# 02-bluetooth-V2_2.net
KiCad netlist of a schematic drawn in Altium Designer
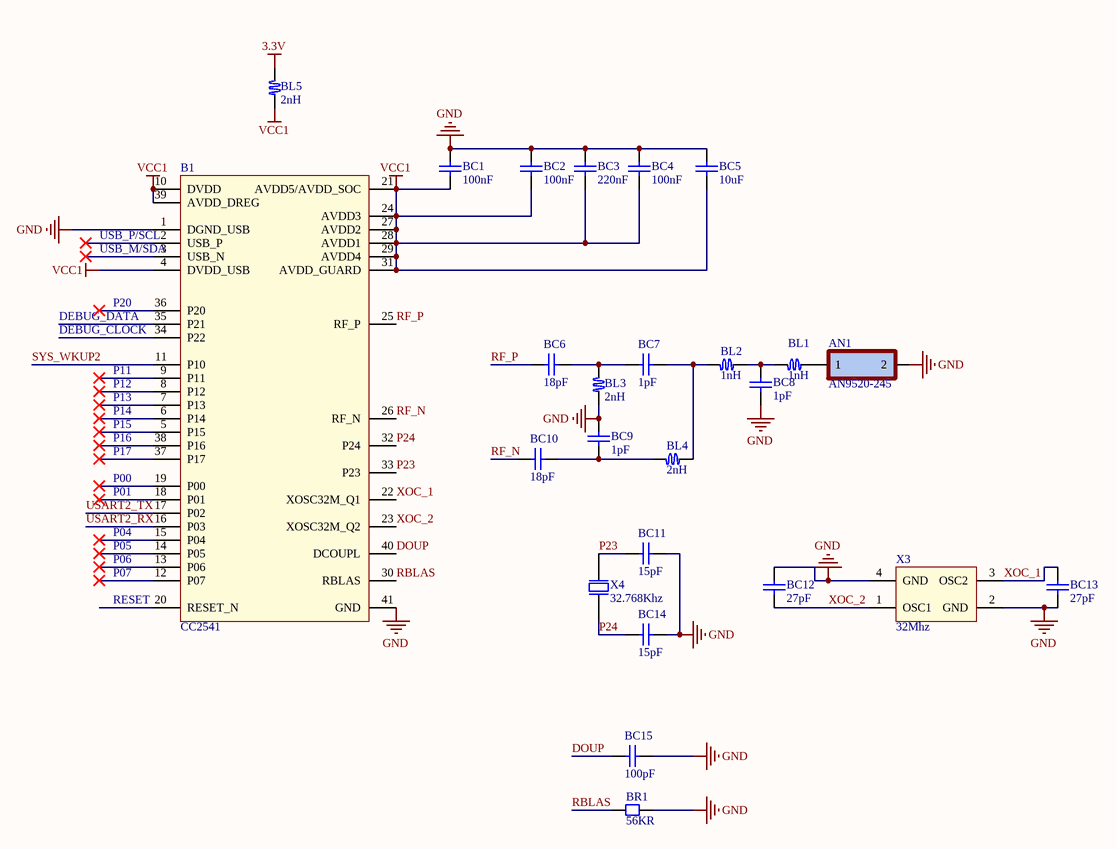
[diagram p0: 02-bluetooth-V2.2.SchDoc]

(export (version "E")
  (design (tool "Eeschema 10.0.6"))
  (components
    (comp (ref "AN1")
      (value "AN9520-245")
      (footprint "AN-5120")
      (description "2.4G全向天线 蓝牙天线 陶瓷贴片 WIFI内置")
      (libsource (lib "tianxiaohua_Schlib") (part "AN9520-245"))
    )
    (comp (ref "B1")
      (value "CC2541")
      (footprint "QFN40-CC254X")
      (description "低功耗蓝牙芯片")
      (libsource (lib "tianxiaohua_Schlib") (part "CC2541"))
    )
    (comp (ref "BC1")
      (value "100nF")
      (footprint "CC1005-0402")
      (description "贴片电容")
      (libsource (lib "tianxiaohua_Schlib") (part "Chip capacitor"))
    )
    (comp (ref "BC2")
      (value "100nF")
      (footprint "CC1005-0402")
      (description "贴片电容")
      (libsource (lib "tianxiaohua_Schlib") (part "Chip capacitor"))
    )
    (comp (ref "BC3")
      (value "220nF")
      (footprint "CC1005-0402")
      (description "贴片电容")
      (libsource (lib "tianxiaohua_Schlib") (part "Chip capacitor"))
    )
    (comp (ref "BC4")
      (value "100nF")
      (footprint "CC1005-0402")
      (description "贴片电容")
      (libsource (lib "tianxiaohua_Schlib") (part "Chip capacitor"))
    )
    (comp (ref "BC5")
      (value "10uF")
      (footprint "CC1005-0402")
      (description "贴片电容")
      (libsource (lib "tianxiaohua_Schlib") (part "Chip capacitor"))
    )
    (comp (ref "BC6")
      (value "18pF")
      (footprint "CC1005-0402")
      (description "贴片电容")
      (libsource (lib "tianxiaohua_Schlib") (part "Chip capacitor"))
    )
    (comp (ref "BC7")
      (value "1pF")
      (footprint "CC1005-0402")
      (description "贴片电容")
      (libsource (lib "tianxiaohua_Schlib") (part "Chip capacitor"))
    )
    (comp (ref "BC8")
      (value "1pF")
      (footprint "CC1005-0402")
      (description "贴片电容")
      (libsource (lib "tianxiaohua_Schlib") (part "Chip capacitor"))
    )
    (comp (ref "BC9")
      (value "1pF")
      (footprint "CC1005-0402")
      (description "贴片电容")
      (libsource (lib "tianxiaohua_Schlib") (part "Chip capacitor"))
    )
    (comp (ref "BC10")
      (value "18pF")
      (footprint "CC1005-0402")
      (description "贴片电容")
      (libsource (lib "tianxiaohua_Schlib") (part "Chip capacitor"))
    )
    (comp (ref "BC11")
      (value "15pF")
      (footprint "CC1005-0402")
      (description "贴片电容")
      (libsource (lib "tianxiaohua_Schlib") (part "Chip capacitor"))
    )
    (comp (ref "BC12")
      (value "27pF")
      (footprint "CC1005-0402")
      (description "贴片电容")
      (libsource (lib "tianxiaohua_Schlib") (part "Chip capacitor"))
    )
    (comp (ref "BC13")
      (value "27pF")
      (footprint "CC1005-0402")
      (description "贴片电容")
      (libsource (lib "tianxiaohua_Schlib") (part "Chip capacitor"))
    )
    (comp (ref "BC14")
      (value "15pF")
      (footprint "CC1005-0402")
      (description "贴片电容")
      (libsource (lib "tianxiaohua_Schlib") (part "Chip capacitor"))
    )
    (comp (ref "BC15")
      (value "100pF")
      (footprint "CC1005-0402")
      (description "贴片电容")
      (libsource (lib "tianxiaohua_Schlib") (part "Chip capacitor"))
    )
    (comp (ref "BL1")
      (value "1nH")
      (footprint "Inductor-0402")
      (description "0402封装的电感")
      (libsource (lib "tianxiaohua_Schlib") (part "Inductor-0402"))
    )
    (comp (ref "BL2")
      (value "1nH")
      (footprint "Inductor-0402")
      (description "0402封装的电感")
      (libsource (lib "tianxiaohua_Schlib") (part "Inductor-0402"))
    )
    (comp (ref "BL3")
      (value "2nH")
      (footprint "Inductor-0402")
      (description "0402封装的电感")
      (libsource (lib "") (part "Inductor-0402_1"))
    )
    (comp (ref "BL4")
      (value "2nH")
      (footprint "Inductor-0402")
      (description "0402封装的电感")
      (libsource (lib "tianxiaohua_Schlib") (part "Inductor-0402"))
    )
    (comp (ref "BL5")
      (value "2nH")
      (footprint "Inductor-0402")
      (description "0402封装的电感")
      (libsource (lib "") (part "Inductor-0402_1"))
    )
    (comp (ref "BR1")
      (value "56KR")
      (footprint "CR1005-0402")
      (description "贴片电阻")
      (libsource (lib "tianxiaohua_Schlib") (part "Chip resistor"))
    )
    (comp (ref "X3")
      (value "32Mhz")
      (footprint "XTAL-2016")
      (description "2016封装的晶振")
      (libsource (lib "tianxiaohua_Schlib") (part "XTAL 2016"))
    )
    (comp (ref "X4")
      (value "32.768Khz")
      (footprint "XTAL-2012")
      (description "2012封装的时钟晶振")
      (libsource (lib "tianxiaohua_Schlib") (part "XTAL 2012"))
    )
  )
  (nets
    (net (code "1") (name "/DEBUG_CLOCK") (class "Default")
      (node (ref "B1") (pin "34") (pinfunction "P22_34") (pintype "passive"))
    )
    (net (code "2") (name "/DEBUG_DATA") (class "Default")
      (node (ref "B1") (pin "35") (pinfunction "P21_35") (pintype "passive"))
    )
    (net (code "3") (name "/DOUP") (class "Default")
      (node (ref "B1") (pin "40") (pinfunction "DCOUPL_40") (pintype "passive"))
      (node (ref "BC15") (pin "2") (pinfunction "2_2") (pintype "passive"))
    )
    (net (code "4") (name "/P00") (class "Default")
      (node (ref "B1") (pin "19") (pinfunction "P00_19") (pintype "passive+no_connect"))
    )
    (net (code "5") (name "/P01") (class "Default")
      (node (ref "B1") (pin "18") (pinfunction "P01_18") (pintype "passive+no_connect"))
    )
    (net (code "6") (name "/P04") (class "Default")
      (node (ref "B1") (pin "15") (pinfunction "P04_15") (pintype "passive+no_connect"))
    )
    (net (code "7") (name "/P05") (class "Default")
      (node (ref "B1") (pin "14") (pinfunction "P05_14") (pintype "passive+no_connect"))
    )
    (net (code "8") (name "/P06") (class "Default")
      (node (ref "B1") (pin "13") (pinfunction "P06_13") (pintype "passive+no_connect"))
    )
    (net (code "9") (name "/P07") (class "Default")
      (node (ref "B1") (pin "12") (pinfunction "P07_12") (pintype "passive+no_connect"))
    )
    (net (code "10") (name "/P11") (class "Default")
      (node (ref "B1") (pin "9") (pinfunction "P11_9") (pintype "passive+no_connect"))
    )
    (net (code "11") (name "/P12") (class "Default")
      (node (ref "B1") (pin "8") (pinfunction "P12_8") (pintype "passive+no_connect"))
    )
    (net (code "12") (name "/P13") (class "Default")
      (node (ref "B1") (pin "7") (pinfunction "P13_7") (pintype "passive+no_connect"))
    )
    (net (code "13") (name "/P14") (class "Default")
      (node (ref "B1") (pin "6") (pinfunction "P14_6") (pintype "passive+no_connect"))
    )
    (net (code "14") (name "/P15") (class "Default")
      (node (ref "B1") (pin "5") (pinfunction "P15_5") (pintype "passive+no_connect"))
    )
    (net (code "15") (name "/P16") (class "Default")
      (node (ref "B1") (pin "38") (pinfunction "P16_38") (pintype "passive+no_connect"))
    )
    (net (code "16") (name "/P17") (class "Default")
      (node (ref "B1") (pin "37") (pinfunction "P17_37") (pintype "passive+no_connect"))
    )
    (net (code "17") (name "/P20") (class "Default")
      (node (ref "B1") (pin "36") (pinfunction "P20_36") (pintype "passive+no_connect"))
    )
    (net (code "18") (name "/P23") (class "Default")
      (node (ref "B1") (pin "33") (pinfunction "P23_33") (pintype "passive"))
      (node (ref "BC11") (pin "1") (pinfunction "1_1") (pintype "passive"))
      (node (ref "X4") (pin "2") (pinfunction "2_2") (pintype "passive"))
    )
    (net (code "19") (name "/P24") (class "Default")
      (node (ref "B1") (pin "32") (pinfunction "P24_32") (pintype "passive"))
      (node (ref "BC14") (pin "1") (pinfunction "1_1") (pintype "passive"))
      (node (ref "X4") (pin "1") (pinfunction "1_1") (pintype "passive"))
    )
    (net (code "20") (name "/RBLAS") (class "Default")
      (node (ref "B1") (pin "30") (pinfunction "RBLAS_30") (pintype "passive"))
      (node (ref "BR1") (pin "1") (pinfunction "1_1") (pintype "passive"))
    )
    (net (code "21") (name "/RESET") (class "Default")
      (node (ref "B1") (pin "20") (pinfunction "RESET_N_20") (pintype "passive"))
    )
    (net (code "22") (name "/RF_N") (class "Default")
      (node (ref "B1") (pin "26") (pinfunction "RF_N_26") (pintype "passive"))
      (node (ref "BC10") (pin "2") (pinfunction "2_2") (pintype "passive"))
    )
    (net (code "23") (name "/RF_P") (class "Default")
      (node (ref "B1") (pin "25") (pinfunction "RF_P_25") (pintype "passive"))
      (node (ref "BC6") (pin "2") (pinfunction "2_2") (pintype "passive"))
    )
    (net (code "24") (name "/SYS_WKUP2") (class "Default")
      (node (ref "B1") (pin "11") (pinfunction "P10_11") (pintype "passive"))
    )
    (net (code "25") (name "/USART2_RX") (class "Default")
      (node (ref "B1") (pin "16") (pinfunction "P03_16") (pintype "passive"))
    )
    (net (code "26") (name "/USART2_TX") (class "Default")
      (node (ref "B1") (pin "17") (pinfunction "P02_17") (pintype "passive"))
    )
    (net (code "27") (name "/USB_M{slash}SDA") (class "Default")
      (node (ref "B1") (pin "3") (pinfunction "USB_N_3") (pintype "passive+no_connect"))
    )
    (net (code "28") (name "/USB_P{slash}SCL") (class "Default")
      (node (ref "B1") (pin "2") (pinfunction "USB_P_2") (pintype "passive+no_connect"))
    )
    (net (code "29") (name "/XOC_1") (class "Default")
      (node (ref "B1") (pin "22") (pinfunction "XOSC32M_Q1_22") (pintype "passive"))
      (node (ref "BC13") (pin "2") (pinfunction "2_2") (pintype "passive"))
      (node (ref "X3") (pin "3") (pinfunction "OSC2_3") (pintype "passive"))
    )
    (net (code "30") (name "/XOC_2") (class "Default")
      (node (ref "B1") (pin "23") (pinfunction "XOSC32M_Q2_23") (pintype "passive"))
      (node (ref "BC12") (pin "1") (pinfunction "1_1") (pintype "passive"))
      (node (ref "X3") (pin "1") (pinfunction "OSC1_1") (pintype "passive"))
    )
    (net (code "31") (name "3.3V") (class "Default")
      (node (ref "BL5") (pin "2") (pinfunction "2_2") (pintype "passive"))
    )
    (net (code "32") (name "GND") (class "Default")
      (node (ref "AN1") (pin "2") (pinfunction "2_2") (pintype "passive"))
      (node (ref "B1") (pin "1") (pinfunction "DGND_USB_1") (pintype "passive"))
      (node (ref "B1") (pin "41") (pinfunction "GND_41") (pintype "passive"))
      (node (ref "BC1") (pin "2") (pinfunction "2_2") (pintype "passive"))
      (node (ref "BC11") (pin "2") (pinfunction "2_2") (pintype "passive"))
      (node (ref "BC12") (pin "2") (pinfunction "2_2") (pintype "passive"))
      (node (ref "BC13") (pin "1") (pinfunction "1_1") (pintype "passive"))
      (node (ref "BC14") (pin "2") (pinfunction "2_2") (pintype "passive"))
      (node (ref "BC15") (pin "1") (pinfunction "1_1") (pintype "passive"))
      (node (ref "BC2") (pin "2") (pinfunction "2_2") (pintype "passive"))
      (node (ref "BC3") (pin "2") (pinfunction "2_2") (pintype "passive"))
      (node (ref "BC4") (pin "2") (pinfunction "2_2") (pintype "passive"))
      (node (ref "BC5") (pin "2") (pinfunction "2_2") (pintype "passive"))
      (node (ref "BC8") (pin "1") (pinfunction "1_1") (pintype "passive"))
      (node (ref "BC9") (pin "1") (pinfunction "1_1") (pintype "passive"))
      (node (ref "BL3") (pin "1") (pinfunction "1_1") (pintype "passive"))
      (node (ref "BR1") (pin "2") (pinfunction "2_2") (pintype "passive"))
      (node (ref "X3") (pin "2") (pinfunction "GND_2") (pintype "passive"))
      (node (ref "X3") (pin "4") (pinfunction "GND_4") (pintype "passive"))
    )
    (net (code "33") (name "Net-(AN1-Pad1)") (class "Default")
      (node (ref "AN1") (pin "1") (pinfunction "1_1") (pintype "passive"))
      (node (ref "BL1") (pin "1") (pinfunction "1_1") (pintype "passive"))
    )
    (net (code "34") (name "Net-(BC6-Pad1)") (class "Default")
      (node (ref "BC6") (pin "1") (pinfunction "1_1") (pintype "passive"))
      (node (ref "BC7") (pin "1") (pinfunction "1_1") (pintype "passive"))
      (node (ref "BL3") (pin "2") (pinfunction "2_2") (pintype "passive"))
    )
    (net (code "35") (name "Net-(BC7-Pad2)") (class "Default")
      (node (ref "BC7") (pin "2") (pinfunction "2_2") (pintype "passive"))
      (node (ref "BL2") (pin "2") (pinfunction "2_2") (pintype "passive"))
      (node (ref "BL4") (pin "1") (pinfunction "1_1") (pintype "passive"))
    )
    (net (code "36") (name "Net-(BC8-Pad2)") (class "Default")
      (node (ref "BC8") (pin "2") (pinfunction "2_2") (pintype "passive"))
      (node (ref "BL1") (pin "2") (pinfunction "2_2") (pintype "passive"))
      (node (ref "BL2") (pin "1") (pinfunction "1_1") (pintype "passive"))
    )
    (net (code "37") (name "Net-(BC10-Pad1)") (class "Default")
      (node (ref "BC10") (pin "1") (pinfunction "1_1") (pintype "passive"))
      (node (ref "BC9") (pin "2") (pinfunction "2_2") (pintype "passive"))
      (node (ref "BL4") (pin "2") (pinfunction "2_2") (pintype "passive"))
    )
    (net (code "38") (name "VCC1") (class "Default")
      (node (ref "B1") (pin "10") (pinfunction "DVDD_10") (pintype "passive"))
      (node (ref "B1") (pin "21") (pinfunction "AVDD5/AVDD_SOC_21") (pintype "passive"))
      (node (ref "B1") (pin "24") (pinfunction "AVDD3_24") (pintype "passive"))
      (node (ref "B1") (pin "27") (pinfunction "AVDD2_27") (pintype "passive"))
      (node (ref "B1") (pin "28") (pinfunction "AVDD1_28") (pintype "passive"))
      (node (ref "B1") (pin "29") (pinfunction "AVDD4_29") (pintype "passive"))
      (node (ref "B1") (pin "31") (pinfunction "AVDD_GUARD_31") (pintype "passive"))
      (node (ref "B1") (pin "39") (pinfunction "AVDD_DREG_39") (pintype "passive"))
      (node (ref "B1") (pin "4") (pinfunction "DVDD_USB_4") (pintype "passive"))
      (node (ref "BC1") (pin "1") (pinfunction "1_1") (pintype "passive"))
      (node (ref "BC2") (pin "1") (pinfunction "1_1") (pintype "passive"))
      (node (ref "BC3") (pin "1") (pinfunction "1_1") (pintype "passive"))
      (node (ref "BC4") (pin "1") (pinfunction "1_1") (pintype "passive"))
      (node (ref "BC5") (pin "1") (pinfunction "1_1") (pintype "passive"))
      (node (ref "BL5") (pin "1") (pinfunction "1_1") (pintype "passive"))
    )
  )
)
